# Adc.net
KiCad netlist of a schematic drawn in Altium Designer
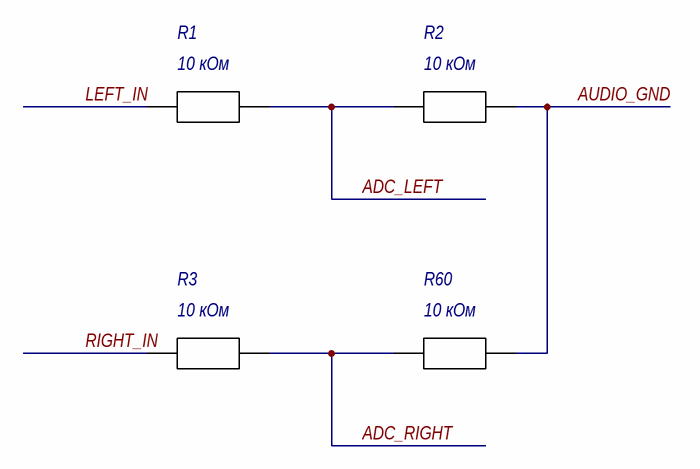
[diagram p0: Adc.SchDoc]

(export (version "E")
  (design (tool "Eeschema 10.0.6"))
  (components
    (comp (ref "R1") (value "10 кОм") (footprint "RES 0805") (libsource (lib "my_lib") (part "RES 0805")))
    (comp (ref "R2") (value "10 кОм") (footprint "RES 0805") (libsource (lib "my_lib") (part "RES 0805")))
    (comp (ref "R3") (value "10 кОм") (footprint "RES 0805") (libsource (lib "my_lib") (part "RES 0805")))
    (comp (ref "R60") (value "10 кОм") (footprint "RES 0805") (libsource (lib "my_lib") (part "RES 0805")))
  )
  (nets
    (net (code "1") (name "/ADC_LEFT") (class "Default")
      (node (ref "R1") (pin "1") (pinfunction "1_1") (pintype "passive"))
      (node (ref "R2") (pin "2") (pinfunction "2_2") (pintype "passive"))
    )
    (net (code "2") (name "/ADC_RIGHT") (class "Default")
      (node (ref "R3") (pin "1") (pinfunction "1_1") (pintype "passive"))
      (node (ref "R60") (pin "2") (pinfunction "2_2") (pintype "passive"))
    )
    (net (code "3") (name "/AUDIO_GND") (class "Default")
      (node (ref "R2") (pin "1") (pinfunction "1_1") (pintype "passive"))
      (node (ref "R60") (pin "1") (pinfunction "1_1") (pintype "passive"))
    )
    (net (code "4") (name "/LEFT_IN") (class "Default")
      (node (ref "R1") (pin "2") (pinfunction "2_2") (pintype "passive"))
    )
    (net (code "5") (name "/RIGHT_IN") (class "Default")
      (node (ref "R3") (pin "2") (pinfunction "2_2") (pintype "passive"))
    )
  )
)
